# RFID_reader_v2.net
KiCad netlist of a schematic drawn in EAGLE
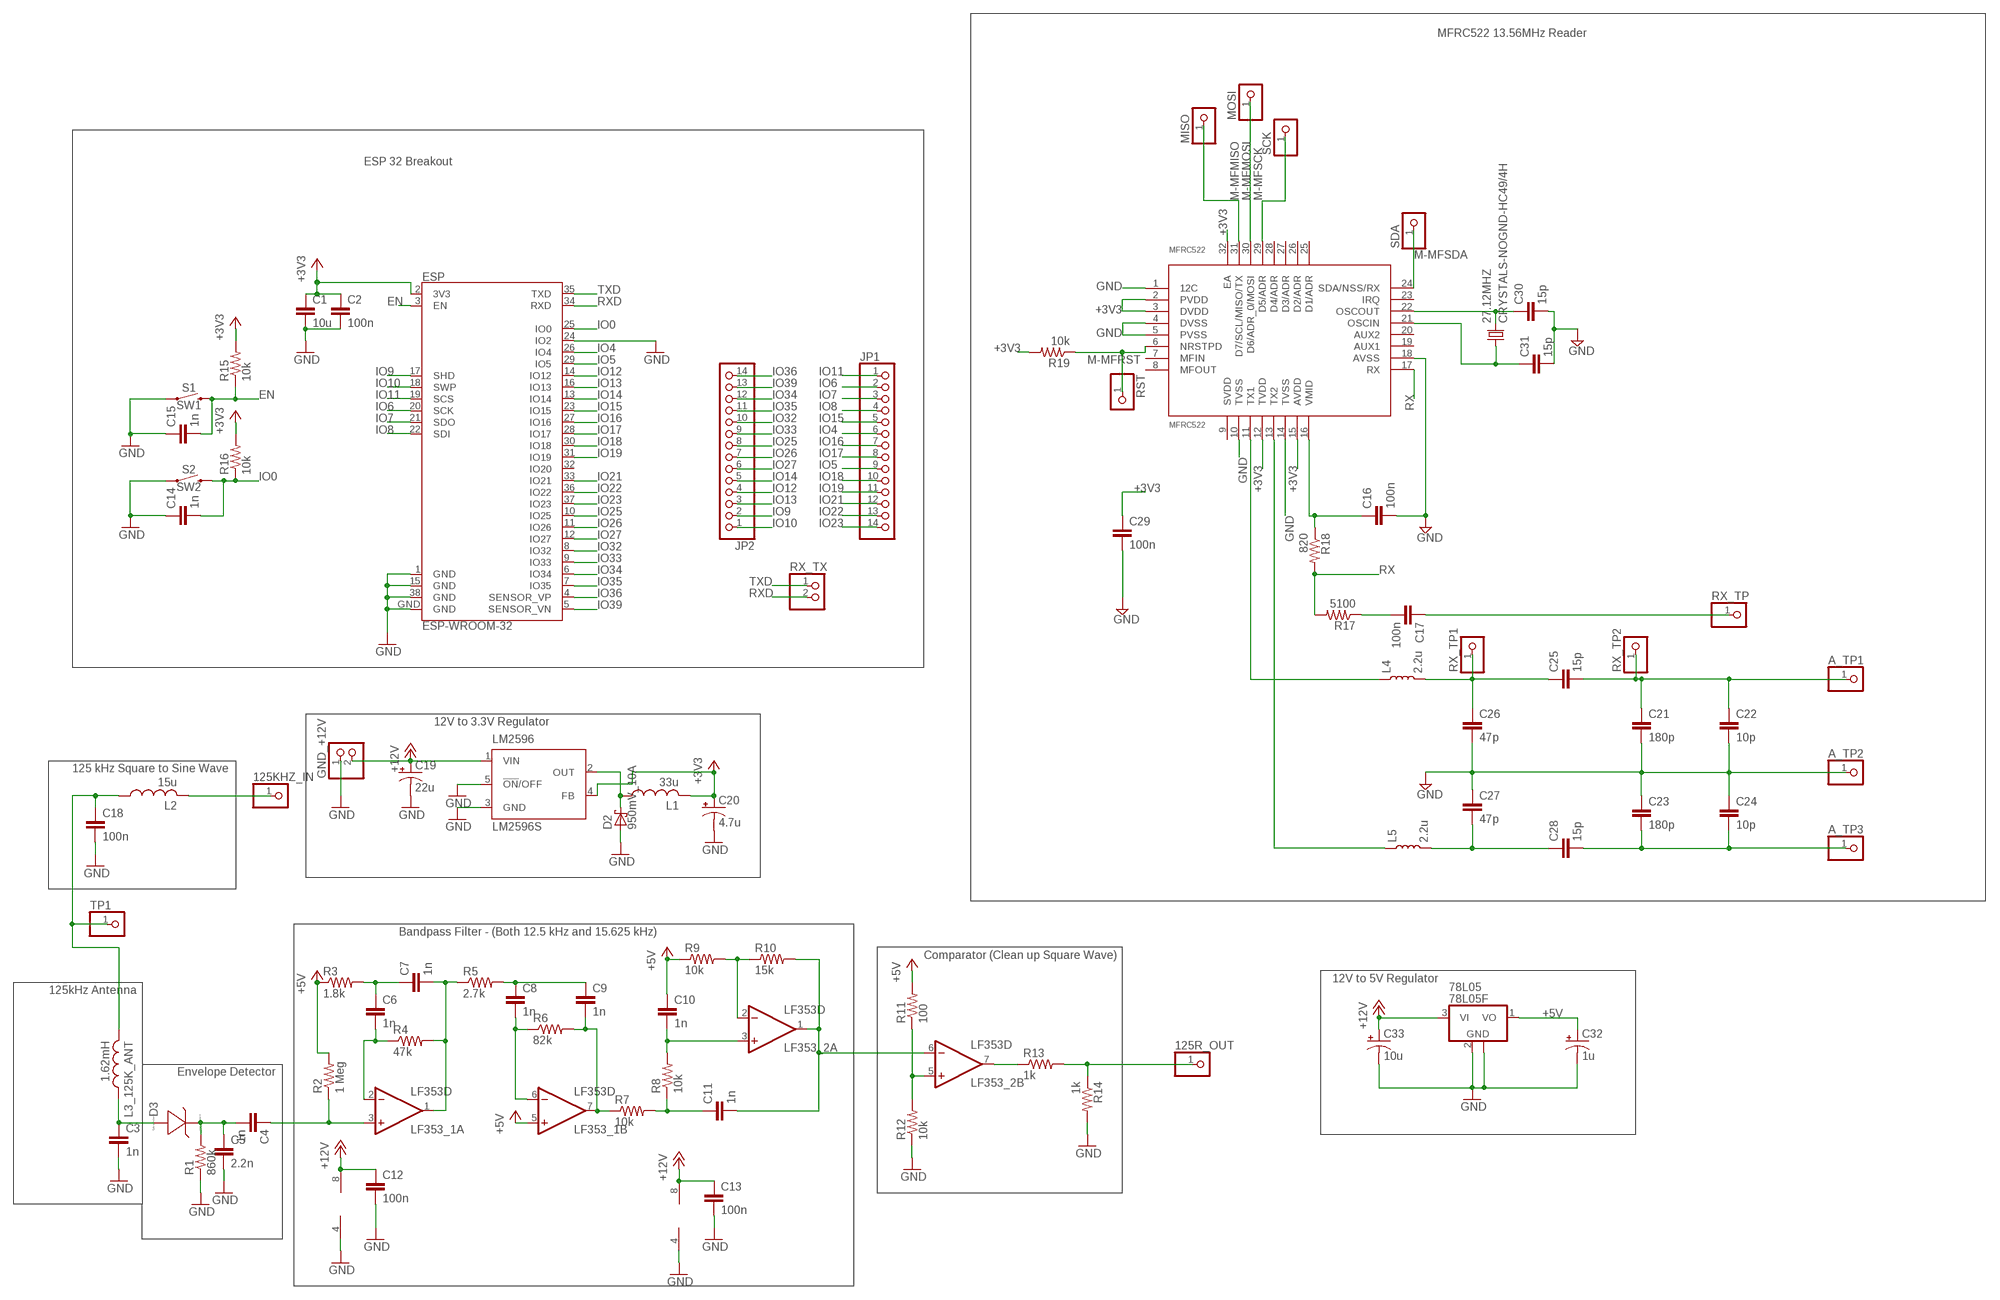
[diagram p0: schematic, sheet 1]

(export (version "E")
  (design (tool "Eeschema 10.0.6"))
  (components
    (comp (ref "27.12MHZ")
      (value "CRYSTALS-NOGND-HC49/4H")
      (footprint "eagle-import:HC49")
      (libsource (lib "eagle-import") (part "CRYSTALS-NOGND-HC49/4H"))
    )
    (comp (ref "78L05")
      (value "78L05F")
      (footprint "eagle-import:SOT89")
      (libsource (lib "eagle-import") (part "78LF05"))
    )
    (comp (ref "125KHZ_IN")
      (value "PINHD-1X1")
      (footprint "eagle-import:1X01")
      (libsource (lib "eagle-import") (part "PINHD-1X1"))
    )
    (comp (ref "125R_OUT")
      (value "PINHD-1X1")
      (footprint "eagle-import:1X01")
      (libsource (lib "eagle-import") (part "PINHD-1X1"))
    )
    (comp (ref "A_TP1")
      (value "PINHD-1X1")
      (footprint "eagle-import:1X01")
      (libsource (lib "eagle-import") (part "PINHD-1X1"))
    )
    (comp (ref "A_TP2")
      (value "PINHD-1X1")
      (footprint "eagle-import:1X01")
      (libsource (lib "eagle-import") (part "PINHD-1X1"))
    )
    (comp (ref "A_TP3")
      (value "PINHD-1X1")
      (footprint "eagle-import:1X01")
      (libsource (lib "eagle-import") (part "PINHD-1X1"))
    )
    (comp (ref "C1")
      (value "10u")
      (footprint "eagle-import:C0805")
      (libsource (lib "eagle-import") (part "C-EUC0805"))
    )
    (comp (ref "C2")
      (value "100n")
      (footprint "eagle-import:C0805")
      (libsource (lib "eagle-import") (part "C-EUC0805"))
    )
    (comp (ref "C3")
      (value "1n")
      (footprint "eagle-import:C0805")
      (libsource (lib "eagle-import") (part "C-EUC0805"))
    )
    (comp (ref "C4")
      (value "1n")
      (footprint "eagle-import:C0805")
      (libsource (lib "eagle-import") (part "C-EUC0805"))
    )
    (comp (ref "C5")
      (value "2.2n")
      (footprint "eagle-import:C0805")
      (libsource (lib "eagle-import") (part "C-EUC0805"))
    )
    (comp (ref "C6")
      (value "1n")
      (footprint "eagle-import:C0805")
      (libsource (lib "eagle-import") (part "C-EUC0805"))
    )
    (comp (ref "C7")
      (value "1n")
      (footprint "eagle-import:C0805")
      (libsource (lib "eagle-import") (part "C-EUC0805"))
    )
    (comp (ref "C8")
      (value "1n")
      (footprint "eagle-import:C0805")
      (libsource (lib "eagle-import") (part "C-EUC0805"))
    )
    (comp (ref "C9")
      (value "1n")
      (footprint "eagle-import:C0805")
      (libsource (lib "eagle-import") (part "C-EUC0805"))
    )
    (comp (ref "C10")
      (value "1n")
      (footprint "eagle-import:C0805")
      (libsource (lib "eagle-import") (part "C-EUC0805"))
    )
    (comp (ref "C11")
      (value "1n")
      (footprint "eagle-import:C0805")
      (libsource (lib "eagle-import") (part "C-EUC0805"))
    )
    (comp (ref "C12")
      (value "100n")
      (footprint "eagle-import:C0805")
      (libsource (lib "eagle-import") (part "C-EUC0805"))
    )
    (comp (ref "C13")
      (value "100n")
      (footprint "eagle-import:C0805")
      (libsource (lib "eagle-import") (part "C-EUC0805"))
    )
    (comp (ref "C14")
      (value "1n")
      (footprint "eagle-import:C0805")
      (libsource (lib "eagle-import") (part "C-EUC0805"))
    )
    (comp (ref "C15")
      (value "1n")
      (footprint "eagle-import:C0805")
      (libsource (lib "eagle-import") (part "C-EUC0805"))
    )
    (comp (ref "C16")
      (value "100n")
      (footprint "eagle-import:C0603")
      (libsource (lib "eagle-import") (part "C-EUC0603"))
    )
    (comp (ref "C17")
      (value "100n")
      (footprint "eagle-import:C0603")
      (libsource (lib "eagle-import") (part "C-EUC0603"))
    )
    (comp (ref "C18")
      (value "100n")
      (footprint "eagle-import:C0805")
      (libsource (lib "eagle-import") (part "C-EUC0805"))
    )
    (comp (ref "C19")
      (value "22u")
      (footprint "eagle-import:SANYO-OSCON_SMD_B6")
      (libsource (lib "eagle-import") (part "CPOL-USSANYO_SMD_B6"))
    )
    (comp (ref "C20")
      (value "4.7u")
      (footprint "eagle-import:SMC_C")
      (libsource (lib "eagle-import") (part "CPOL-USSMCC"))
    )
    (comp (ref "C21")
      (value "180p")
      (footprint "eagle-import:C0603")
      (libsource (lib "eagle-import") (part "C-EUC0603"))
    )
    (comp (ref "C22")
      (value "10p")
      (footprint "eagle-import:C0603")
      (libsource (lib "eagle-import") (part "C-EUC0603"))
    )
    (comp (ref "C23")
      (value "180p")
      (footprint "eagle-import:C0603")
      (libsource (lib "eagle-import") (part "C-EUC0603"))
    )
    (comp (ref "C24")
      (value "10p")
      (footprint "eagle-import:C0603")
      (libsource (lib "eagle-import") (part "C-EUC0603"))
    )
    (comp (ref "C25")
      (value "15p")
      (footprint "eagle-import:C0603")
      (libsource (lib "eagle-import") (part "C-EUC0603"))
    )
    (comp (ref "C26")
      (value "47p")
      (footprint "eagle-import:C0603")
      (libsource (lib "eagle-import") (part "C-EUC0603"))
    )
    (comp (ref "C27")
      (value "47p")
      (footprint "eagle-import:C0603")
      (libsource (lib "eagle-import") (part "C-EUC0603"))
    )
    (comp (ref "C28")
      (value "15p")
      (footprint "eagle-import:C0603")
      (libsource (lib "eagle-import") (part "C-EUC0603"))
    )
    (comp (ref "C29")
      (value "100n")
      (footprint "eagle-import:C0603")
      (libsource (lib "eagle-import") (part "C-EUC0603"))
    )
    (comp (ref "C30")
      (value "15p")
      (footprint "eagle-import:C0603")
      (libsource (lib "eagle-import") (part "C-EUC0603"))
    )
    (comp (ref "C31")
      (value "15p")
      (footprint "eagle-import:C0603")
      (libsource (lib "eagle-import") (part "C-EUC0603"))
    )
    (comp (ref "C32")
      (value "1u")
      (footprint "eagle-import:SMC_A")
      (libsource (lib "eagle-import") (part "CPOL-USSMCA"))
    )
    (comp (ref "C33")
      (value "10u")
      (footprint "eagle-import:SMC_C")
      (libsource (lib "eagle-import") (part "CPOL-USSMCC"))
    )
    (comp (ref "D2")
      (value "950mV_10A")
      (footprint "eagle-import:SMC")
      (libsource (lib "eagle-import") (part "SCHOTTKY-DIODESMC"))
    )
    (comp (ref "D3")
      (value "ZENER")
      (footprint "eagle-import:SOD123")
      (libsource (lib "eagle-import") (part "ZENER"))
    )
    (comp (ref "ESP")
      (value "ESP-WROOM-32")
      (footprint "eagle-import:ESP-WROOM-32")
      (libsource (lib "eagle-import") (part "ESP-WROOM-32"))
    )
    (comp (ref "GND_+12V")
      (value "PINHD-1X2")
      (footprint "eagle-import:1X02")
      (libsource (lib "eagle-import") (part "PINHD-1X2"))
    )
    (comp (ref "JP1")
      (value "PINHD-1X14")
      (footprint "eagle-import:1X14")
      (libsource (lib "eagle-import") (part "PINHD-1X14"))
    )
    (comp (ref "JP2")
      (value "PINHD-1X14")
      (footprint "eagle-import:1X14")
      (libsource (lib "eagle-import") (part "PINHD-1X14"))
    )
    (comp (ref "L1")
      (value "33u")
      (footprint "eagle-import:0207_10")
      (libsource (lib "eagle-import") (part "L-US0207/10"))
    )
    (comp (ref "L2")
      (value "15u")
      (footprint "eagle-import:L2012C")
      (libsource (lib "eagle-import") (part "L-USL2012C"))
    )
    (comp (ref "L3_125K_ANT")
      (value "1.62mH")
      (footprint "eagle-import:0207_10")
      (libsource (lib "eagle-import") (part "L-US0207/10"))
    )
    (comp (ref "L4")
      (value "2.2u")
      (footprint "eagle-import:0603")
      (libsource (lib "eagle-import") (part "INDUCTOR-0603-33NH"))
    )
    (comp (ref "L5")
      (value "2.2u")
      (footprint "eagle-import:0603")
      (libsource (lib "eagle-import") (part "INDUCTOR-0603-33NH"))
    )
    (comp (ref "LF353_1")
      (value "LF353D")
      (footprint "eagle-import:SO08")
      (fields (field (name "SPICEPREFIX") "J"))
      (libsource (lib "eagle-import") (part "LF353D"))
    )
    (comp (ref "LF353_2")
      (value "LF353D")
      (footprint "eagle-import:SO08")
      (libsource (lib "eagle-import") (part "LF353D"))
    )
    (comp (ref "LM2596")
      (value "LM2596S")
      (footprint "eagle-import:TO263-5")
      (fields (field (name "MF") "NATIONAL SEMICONDUCTOR") (field (name "MPN") "LM2596S-ADJ/NOPB"))
      (libsource (lib "eagle-import") (part "LM2596S"))
    )
    (comp (ref "MFRC522")
      (value "MFRC522")
      (footprint "eagle-import:MFR522")
      (libsource (lib "eagle-import") (part "MFRC522"))
    )
    (comp (ref "MISO")
      (value "PINHD-1X1")
      (footprint "eagle-import:1X01")
      (libsource (lib "eagle-import") (part "PINHD-1X1"))
    )
    (comp (ref "MOSI")
      (value "PINHD-1X1")
      (footprint "eagle-import:1X01")
      (libsource (lib "eagle-import") (part "PINHD-1X1"))
    )
    (comp (ref "R1")
      (value "860k")
      (footprint "eagle-import:R0805")
      (libsource (lib "eagle-import") (part "R-US_R0805"))
    )
    (comp (ref "R2")
      (value "1 Meg")
      (footprint "eagle-import:R0805")
      (libsource (lib "eagle-import") (part "R-US_R0805"))
    )
    (comp (ref "R3")
      (value "1.8k")
      (footprint "eagle-import:R0805")
      (libsource (lib "eagle-import") (part "R-US_R0805"))
    )
    (comp (ref "R4")
      (value "47k")
      (footprint "eagle-import:R0805")
      (libsource (lib "eagle-import") (part "R-US_R0805"))
    )
    (comp (ref "R5")
      (value "2.7k")
      (footprint "eagle-import:R0805")
      (libsource (lib "eagle-import") (part "R-US_R0805"))
    )
    (comp (ref "R6")
      (value "82k")
      (footprint "eagle-import:R0805")
      (libsource (lib "eagle-import") (part "R-US_R0805"))
    )
    (comp (ref "R7")
      (value "10k")
      (footprint "eagle-import:R0805")
      (libsource (lib "eagle-import") (part "R-US_R0805"))
    )
    (comp (ref "R8")
      (value "10k")
      (footprint "eagle-import:R0805")
      (libsource (lib "eagle-import") (part "R-US_R0805"))
    )
    (comp (ref "R9")
      (value "10k")
      (footprint "eagle-import:R0805")
      (libsource (lib "eagle-import") (part "R-US_R0805"))
    )
    (comp (ref "R10")
      (value "15k")
      (footprint "eagle-import:R0805")
      (libsource (lib "eagle-import") (part "R-US_R0805"))
    )
    (comp (ref "R11")
      (value "100")
      (footprint "eagle-import:R0805")
      (libsource (lib "eagle-import") (part "R-US_R0805"))
    )
    (comp (ref "R12")
      (value "10k")
      (footprint "eagle-import:R0805")
      (libsource (lib "eagle-import") (part "R-US_R0805"))
    )
    (comp (ref "R13")
      (value "1k")
      (footprint "eagle-import:R0805")
      (libsource (lib "eagle-import") (part "R-US_R0805"))
    )
    (comp (ref "R14")
      (value "1k")
      (footprint "eagle-import:R0805")
      (libsource (lib "eagle-import") (part "R-US_R0805"))
    )
    (comp (ref "R15")
      (value "10k")
      (footprint "eagle-import:R0805")
      (libsource (lib "eagle-import") (part "R-US_R0805"))
    )
    (comp (ref "R16")
      (value "10k")
      (footprint "eagle-import:R0805")
      (libsource (lib "eagle-import") (part "R-US_R0805"))
    )
    (comp (ref "R17")
      (value "5100")
      (footprint "eagle-import:R0603")
      (libsource (lib "eagle-import") (part "R-US_R0603"))
    )
    (comp (ref "R18")
      (value "820")
      (footprint "eagle-import:R0603")
      (libsource (lib "eagle-import") (part "R-US_R0603"))
    )
    (comp (ref "R19")
      (value "10k")
      (footprint "eagle-import:R0603")
      (libsource (lib "eagle-import") (part "R-US_R0603"))
    )
    (comp (ref "RST")
      (value "PINHD-1X1")
      (footprint "eagle-import:1X01")
      (libsource (lib "eagle-import") (part "PINHD-1X1"))
    )
    (comp (ref "RX_TP")
      (value "PINHD-1X1")
      (footprint "eagle-import:1X01")
      (libsource (lib "eagle-import") (part "PINHD-1X1"))
    )
    (comp (ref "RX_TP1")
      (value "PINHD-1X1")
      (footprint "eagle-import:1X01")
      (libsource (lib "eagle-import") (part "PINHD-1X1"))
    )
    (comp (ref "RX_TP2")
      (value "PINHD-1X1")
      (footprint "eagle-import:1X01")
      (libsource (lib "eagle-import") (part "PINHD-1X1"))
    )
    (comp (ref "RX_TX")
      (value "PINHD-1X2")
      (footprint "eagle-import:1X02")
      (libsource (lib "eagle-import") (part "PINHD-1X2"))
    )
    (comp (ref "S1")
      (value "SW1")
      (footprint "eagle-import:TACTILE_SWITCH_SMD_6.0X3.5MM")
      (libsource (lib "eagle-import") (part "MOMENTARY-SWITCH-SPST-SMD-6.0X3.5MM"))
    )
    (comp (ref "S2")
      (value "SW2")
      (footprint "eagle-import:TACTILE_SWITCH_SMD_6.0X3.5MM")
      (libsource (lib "eagle-import") (part "MOMENTARY-SWITCH-SPST-SMD-6.0X3.5MM"))
    )
    (comp (ref "SCK")
      (value "PINHD-1X1")
      (footprint "eagle-import:1X01")
      (libsource (lib "eagle-import") (part "PINHD-1X1"))
    )
    (comp (ref "SDA")
      (value "PINHD-1X1")
      (footprint "eagle-import:1X01")
      (libsource (lib "eagle-import") (part "PINHD-1X1"))
    )
    (comp (ref "TP1")
      (value "PINHD-1X1")
      (footprint "eagle-import:1X01")
      (libsource (lib "eagle-import") (part "PINHD-1X1"))
    )
  )
  (nets
    (net (code "1") (name "+3V3") (class "Default")
      (node (ref "C1") (pin "1") (pinfunction "1_1") (pintype "passive"))
      (node (ref "C2") (pin "1") (pinfunction "1_1") (pintype "passive"))
      (node (ref "C20") (pin "+") (pinfunction "+_+") (pintype "passive"))
      (node (ref "C29") (pin "1") (pinfunction "1_1") (pintype "passive"))
      (node (ref "ESP") (pin "2") (pinfunction "3V3_2") (pintype "bidirectional"))
      (node (ref "L1") (pin "2") (pinfunction "2_2") (pintype "passive"))
      (node (ref "LM2596") (pin "4") (pinfunction "FB_4") (pintype "input"))
      (node (ref "MFRC522") (pin "12") (pinfunction "TVDD_12") (pintype "bidirectional"))
      (node (ref "MFRC522") (pin "15") (pinfunction "AVDD_15") (pintype "bidirectional"))
      (node (ref "MFRC522") (pin "2") (pinfunction "PVDD_2") (pintype "bidirectional"))
      (node (ref "MFRC522") (pin "3") (pinfunction "DVDD_3") (pintype "bidirectional"))
      (node (ref "MFRC522") (pin "32") (pinfunction "EA_32") (pintype "bidirectional"))
      (node (ref "R15") (pin "2") (pinfunction "2_2") (pintype "passive"))
      (node (ref "R16") (pin "2") (pinfunction "2_2") (pintype "passive"))
      (node (ref "R19") (pin "2") (pinfunction "2_2") (pintype "passive"))
    )
    (net (code "2") (name "+5V") (class "Default")
      (node (ref "78L05") (pin "1") (pinfunction "VO_1") (pintype "passive"))
      (node (ref "C10") (pin "1") (pinfunction "1_1") (pintype "passive"))
      (node (ref "C32") (pin "+") (pinfunction "+_+") (pintype "passive"))
      (node (ref "LF353_1") (pin "5") (pinfunction "+IN_5") (pintype "input"))
      (node (ref "R11") (pin "2") (pinfunction "2_2") (pintype "passive"))
      (node (ref "R2") (pin "2") (pinfunction "2_2") (pintype "passive"))
      (node (ref "R3") (pin "1") (pinfunction "1_1") (pintype "passive"))
      (node (ref "R9") (pin "1") (pinfunction "1_1") (pintype "passive"))
    )
    (net (code "3") (name "+12V") (class "Default")
      (node (ref "78L05") (pin "3") (pinfunction "VI_3") (pintype "input"))
      (node (ref "C12") (pin "1") (pinfunction "1_1") (pintype "passive"))
      (node (ref "C13") (pin "1") (pinfunction "1_1") (pintype "passive"))
      (node (ref "C19") (pin "+") (pinfunction "+_+") (pintype "passive"))
      (node (ref "C33") (pin "+") (pinfunction "+_+") (pintype "passive"))
      (node (ref "GND_+12V") (pin "2") (pinfunction "2_2") (pintype "passive"))
      (node (ref "LF353_1") (pin "8") (pinfunction "V+_8") (pintype "power_in"))
      (node (ref "LF353_2") (pin "8") (pinfunction "V+_8") (pintype "power_in"))
      (node (ref "LM2596") (pin "1") (pinfunction "VIN_1") (pintype "input"))
    )
    (net (code "4") (name "/EN") (class "Default")
      (node (ref "C15") (pin "2") (pinfunction "2_2") (pintype "passive"))
      (node (ref "ESP") (pin "3") (pinfunction "EN_3") (pintype "bidirectional"))
      (node (ref "R15") (pin "1") (pinfunction "1_1") (pintype "passive"))
      (node (ref "S1") (pin "2") (pinfunction "2_2") (pintype "passive"))
    )
    (net (code "5") (name "/IO0") (class "Default")
      (node (ref "C14") (pin "2") (pinfunction "2_2") (pintype "passive"))
      (node (ref "ESP") (pin "25") (pinfunction "IO0_25") (pintype "bidirectional"))
      (node (ref "R16") (pin "1") (pinfunction "1_1") (pintype "passive"))
      (node (ref "S2") (pin "2") (pinfunction "2_2") (pintype "passive"))
    )
    (net (code "6") (name "/IO4") (class "Default")
      (node (ref "ESP") (pin "26") (pinfunction "IO4_26") (pintype "bidirectional"))
      (node (ref "JP1") (pin "6") (pinfunction "6_6") (pintype "passive"))
    )
    (net (code "7") (name "/IO5") (class "Default")
      (node (ref "ESP") (pin "29") (pinfunction "IO5_29") (pintype "bidirectional"))
      (node (ref "JP1") (pin "9") (pinfunction "9_9") (pintype "passive"))
    )
    (net (code "8") (name "/IO6") (class "Default")
      (node (ref "ESP") (pin "20") (pinfunction "SCK_20") (pintype "bidirectional"))
      (node (ref "JP1") (pin "2") (pinfunction "2_2") (pintype "passive"))
    )
    (net (code "9") (name "/IO7") (class "Default")
      (node (ref "ESP") (pin "21") (pinfunction "SDO_21") (pintype "bidirectional"))
      (node (ref "JP1") (pin "3") (pinfunction "3_3") (pintype "passive"))
    )
    (net (code "10") (name "/IO8") (class "Default")
      (node (ref "ESP") (pin "22") (pinfunction "SDI_22") (pintype "bidirectional"))
      (node (ref "JP1") (pin "4") (pinfunction "4_4") (pintype "passive"))
    )
    (net (code "11") (name "/IO9") (class "Default")
      (node (ref "ESP") (pin "17") (pinfunction "SHD_17") (pintype "bidirectional"))
      (node (ref "JP2") (pin "2") (pinfunction "2_2") (pintype "passive"))
    )
    (net (code "12") (name "/IO10") (class "Default")
      (node (ref "ESP") (pin "18") (pinfunction "SWP_18") (pintype "bidirectional"))
      (node (ref "JP2") (pin "1") (pinfunction "1_1") (pintype "passive"))
    )
    (net (code "13") (name "/IO11") (class "Default")
      (node (ref "ESP") (pin "19") (pinfunction "SCS_19") (pintype "bidirectional"))
      (node (ref "JP1") (pin "1") (pinfunction "1_1") (pintype "passive"))
    )
    (net (code "14") (name "/IO12") (class "Default")
      (node (ref "ESP") (pin "14") (pinfunction "IO12_14") (pintype "bidirectional"))
      (node (ref "JP2") (pin "4") (pinfunction "4_4") (pintype "passive"))
    )
    (net (code "15") (name "/IO13") (class "Default")
      (node (ref "ESP") (pin "16") (pinfunction "IO13_16") (pintype "bidirectional"))
      (node (ref "JP2") (pin "3") (pinfunction "3_3") (pintype "passive"))
    )
    (net (code "16") (name "/IO14") (class "Default")
      (node (ref "ESP") (pin "13") (pinfunction "IO14_13") (pintype "bidirectional"))
      (node (ref "JP2") (pin "5") (pinfunction "5_5") (pintype "passive"))
    )
    (net (code "17") (name "/IO15") (class "Default")
      (node (ref "ESP") (pin "23") (pinfunction "IO15_23") (pintype "bidirectional"))
      (node (ref "JP1") (pin "5") (pinfunction "5_5") (pintype "passive"))
    )
    (net (code "18") (name "/IO16") (class "Default")
      (node (ref "ESP") (pin "27") (pinfunction "IO16_27") (pintype "bidirectional"))
      (node (ref "JP1") (pin "7") (pinfunction "7_7") (pintype "passive"))
    )
    (net (code "19") (name "/IO17") (class "Default")
      (node (ref "ESP") (pin "28") (pinfunction "IO17_28") (pintype "bidirectional"))
      (node (ref "JP1") (pin "8") (pinfunction "8_8") (pintype "passive"))
    )
    (net (code "20") (name "/IO18") (class "Default")
      (node (ref "ESP") (pin "30") (pinfunction "IO18_30") (pintype "bidirectional"))
      (node (ref "JP1") (pin "10") (pinfunction "10_10") (pintype "passive"))
    )
    (net (code "21") (name "/IO19") (class "Default")
      (node (ref "ESP") (pin "31") (pinfunction "IO19_31") (pintype "bidirectional"))
      (node (ref "JP1") (pin "11") (pinfunction "11_11") (pintype "passive"))
    )
    (net (code "22") (name "/IO21") (class "Default")
      (node (ref "ESP") (pin "33") (pinfunction "IO21_33") (pintype "bidirectional"))
      (node (ref "JP1") (pin "12") (pinfunction "12_12") (pintype "passive"))
    )
    (net (code "23") (name "/IO22") (class "Default")
      (node (ref "ESP") (pin "36") (pinfunction "IO22_36") (pintype "bidirectional"))
      (node (ref "JP1") (pin "13") (pinfunction "13_13") (pintype "passive"))
    )
    (net (code "24") (name "/IO23") (class "Default")
      (node (ref "ESP") (pin "37") (pinfunction "IO23_37") (pintype "bidirectional"))
      (node (ref "JP1") (pin "14") (pinfunction "14_14") (pintype "passive"))
    )
    (net (code "25") (name "/IO25") (class "Default")
      (node (ref "ESP") (pin "10") (pinfunction "IO25_10") (pintype "bidirectional"))
      (node (ref "JP2") (pin "8") (pinfunction "8_8") (pintype "passive"))
    )
    (net (code "26") (name "/IO26") (class "Default")
      (node (ref "ESP") (pin "11") (pinfunction "IO26_11") (pintype "bidirectional"))
      (node (ref "JP2") (pin "7") (pinfunction "7_7") (pintype "passive"))
    )
    (net (code "27") (name "/IO27") (class "Default")
      (node (ref "ESP") (pin "12") (pinfunction "IO27_12") (pintype "bidirectional"))
      (node (ref "JP2") (pin "6") (pinfunction "6_6") (pintype "passive"))
    )
    (net (code "28") (name "/IO32") (class "Default")
      (node (ref "ESP") (pin "8") (pinfunction "IO32_8") (pintype "bidirectional"))
      (node (ref "JP2") (pin "10") (pinfunction "10_10") (pintype "passive"))
    )
    (net (code "29") (name "/IO33") (class "Default")
      (node (ref "ESP") (pin "9") (pinfunction "IO33_9") (pintype "bidirectional"))
      (node (ref "JP2") (pin "9") (pinfunction "9_9") (pintype "passive"))
    )
    (net (code "30") (name "/IO34") (class "Default")
      (node (ref "ESP") (pin "6") (pinfunction "IO34_6") (pintype "bidirectional"))
      (node (ref "JP2") (pin "12") (pinfunction "12_12") (pintype "passive"))
    )
    (net (code "31") (name "/IO35") (class "Default")
      (node (ref "ESP") (pin "7") (pinfunction "IO35_7") (pintype "bidirectional"))
      (node (ref "JP2") (pin "11") (pinfunction "11_11") (pintype "passive"))
    )
    (net (code "32") (name "/IO36") (class "Default")
      (node (ref "ESP") (pin "4") (pinfunction "SENSOR_VP_4") (pintype "bidirectional"))
      (node (ref "JP2") (pin "14") (pinfunction "14_14") (pintype "passive"))
    )
    (net (code "33") (name "/IO39") (class "Default")
      (node (ref "ESP") (pin "5") (pinfunction "SENSOR_VN_5") (pintype "bidirectional"))
      (node (ref "JP2") (pin "13") (pinfunction "13_13") (pintype "passive"))
    )
    (net (code "34") (name "/M-MFMISO") (class "Default")
      (node (ref "MFRC522") (pin "31") (pinfunction "D7/SCL/MISO/TX_31") (pintype "bidirectional"))
      (node (ref "MISO") (pin "1") (pinfunction "1_1") (pintype "passive"))
    )
    (net (code "35") (name "/M-MFMOSI") (class "Default")
      (node (ref "MFRC522") (pin "30") (pinfunction "D6/ADR_0/MOSI_30") (pintype "bidirectional"))
      (node (ref "MOSI") (pin "1") (pinfunction "1_1") (pintype "passive"))
    )
    (net (code "36") (name "/M-MFRST") (class "Default")
      (node (ref "MFRC522") (pin "6") (pinfunction "NRSTPD_6") (pintype "bidirectional"))
      (node (ref "R19") (pin "1") (pinfunction "1_1") (pintype "passive"))
      (node (ref "RST") (pin "1") (pinfunction "1_1") (pintype "passive"))
    )
    (net (code "37") (name "/M-MFSCK") (class "Default")
      (node (ref "MFRC522") (pin "29") (pinfunction "D5/ADR_29") (pintype "bidirectional"))
      (node (ref "SCK") (pin "1") (pinfunction "1_1") (pintype "passive"))
    )
    (net (code "38") (name "/M-MFSDA") (class "Default")
      (node (ref "MFRC522") (pin "24") (pinfunction "SDA/NSS/RX_24") (pintype "bidirectional"))
      (node (ref "SDA") (pin "1") (pinfunction "1_1") (pintype "passive"))
    )
    (net (code "39") (name "/RX") (class "Default")
      (node (ref "MFRC522") (pin "17") (pinfunction "RX_17") (pintype "bidirectional"))
      (node (ref "R17") (pin "2") (pinfunction "2_2") (pintype "passive"))
      (node (ref "R18") (pin "2") (pinfunction "2_2") (pintype "passive"))
    )
    (net (code "40") (name "/RXD") (class "Default")
      (node (ref "ESP") (pin "34") (pinfunction "RXD_34") (pintype "bidirectional"))
      (node (ref "RX_TX") (pin "2") (pinfunction "2_2") (pintype "passive"))
    )
    (net (code "41") (name "/TXD") (class "Default")
      (node (ref "ESP") (pin "35") (pinfunction "TXD_35") (pintype "bidirectional"))
      (node (ref "RX_TX") (pin "1") (pinfunction "1_1") (pintype "passive"))
    )
    (net (code "42") (name "GND") (class "Default")
      (node (ref "78L05") (pin "2") (pinfunction "GND_2") (pintype "passive"))
      (node (ref "78L05") (pin "2@1") (pinfunction "GND_2@1") (pintype "passive"))
      (node (ref "A_TP2") (pin "1") (pinfunction "1_1") (pintype "passive"))
      (node (ref "C1") (pin "2") (pinfunction "2_2") (pintype "passive"))
      (node (ref "C12") (pin "2") (pinfunction "2_2") (pintype "passive"))
      (node (ref "C13") (pin "2") (pinfunction "2_2") (pintype "passive"))
      (node (ref "C14") (pin "1") (pinfunction "1_1") (pintype "passive"))
      (node (ref "C15") (pin "1") (pinfunction "1_1") (pintype "passive"))
      (node (ref "C16") (pin "2") (pinfunction "2_2") (pintype "passive"))
      (node (ref "C18") (pin "2") (pinfunction "2_2") (pintype "passive"))
      (node (ref "C19") (pin "-") (pinfunction "-_-") (pintype "passive"))
      (node (ref "C2") (pin "2") (pinfunction "2_2") (pintype "passive"))
      (node (ref "C20") (pin "-") (pinfunction "-_-") (pintype "passive"))
      (node (ref "C21") (pin "2") (pinfunction "2_2") (pintype "passive"))
      (node (ref "C22") (pin "2") (pinfunction "2_2") (pintype "passive"))
      (node (ref "C23") (pin "1") (pinfunction "1_1") (pintype "passive"))
      (node (ref "C24") (pin "1") (pinfunction "1_1") (pintype "passive"))
      (node (ref "C26") (pin "2") (pinfunction "2_2") (pintype "passive"))
      (node (ref "C27") (pin "1") (pinfunction "1_1") (pintype "passive"))
      (node (ref "C29") (pin "2") (pinfunction "2_2") (pintype "passive"))
      (node (ref "C3") (pin "2") (pinfunction "2_2") (pintype "passive"))
      (node (ref "C30") (pin "2") (pinfunction "2_2") (pintype "passive"))
      (node (ref "C31") (pin "2") (pinfunction "2_2") (pintype "passive"))
      (node (ref "C32") (pin "-") (pinfunction "-_-") (pintype "passive"))
      (node (ref "C33") (pin "-") (pinfunction "-_-") (pintype "passive"))
      (node (ref "C5") (pin "2") (pinfunction "2_2") (pintype "passive"))
      (node (ref "D2") (pin "A") (pinfunction "A_A") (pintype "passive"))
      (node (ref "ESP") (pin "1") (pinfunction "GND_1") (pintype "bidirectional"))
      (node (ref "ESP") (pin "15") (pinfunction "GND_15") (pintype "bidirectional"))
      (node (ref "ESP") (pin "24") (pinfunction "IO2_24") (pintype "bidirectional"))
      (node (ref "ESP") (pin "38") (pinfunction "GND_38") (pintype "bidirectional"))
      (node (ref "ESP") (pin "GND") (pinfunction "GND_GND") (pintype "bidirectional"))
      (node (ref "GND_+12V") (pin "1") (pinfunction "1_1") (pintype "passive"))
      (node (ref "LF353_1") (pin "4") (pinfunction "V-_4") (pintype "power_in"))
      (node (ref "LF353_2") (pin "4") (pinfunction "V-_4") (pintype "power_in"))
      (node (ref "LM2596") (pin "3") (pinfunction "GND_3") (pintype "power_in"))
      (node (ref "LM2596") (pin "5") (pinfunction "~{ON}/OFF_5") (pintype "input"))
      (node (ref "MFRC522") (pin "1") (pinfunction "12C_1") (pintype "bidirectional"))
      (node (ref "MFRC522") (pin "10") (pinfunction "TVSS_10") (pintype "bidirectional"))
      (node (ref "MFRC522") (pin "14") (pinfunction "TVSS_14") (pintype "bidirectional"))
      (node (ref "MFRC522") (pin "18") (pinfunction "AVSS_18") (pintype "bidirectional"))
      (node (ref "MFRC522") (pin "4") (pinfunction "DVSS_4") (pintype "bidirectional"))
      (node (ref "MFRC522") (pin "5") (pinfunction "PVSS_5") (pintype "bidirectional"))
      (node (ref "R1") (pin "1") (pinfunction "1_1") (pintype "passive"))
      (node (ref "R12") (pin "1") (pinfunction "1_1") (pintype "passive"))
      (node (ref "R14") (pin "2") (pinfunction "2_2") (pintype "passive"))
      (node (ref "S1") (pin "1") (pinfunction "1_1") (pintype "passive"))
      (node (ref "S2") (pin "1") (pinfunction "1_1") (pintype "passive"))
    )
    (net (code "43") (name "Net-(125KHZ_IN-Pad1)") (class "Default")
      (node (ref "125KHZ_IN") (pin "1") (pinfunction "1_1") (pintype "passive"))
      (node (ref "L2") (pin "2") (pinfunction "2_2") (pintype "passive"))
    )
    (net (code "44") (name "Net-(125R_OUT-Pad1)") (class "Default")
      (node (ref "125R_OUT") (pin "1") (pinfunction "1_1") (pintype "passive"))
      (node (ref "R13") (pin "2") (pinfunction "2_2") (pintype "passive"))
      (node (ref "R14") (pin "1") (pinfunction "1_1") (pintype "passive"))
    )
    (net (code "45") (name "Net-(A_TP1-Pad1)") (class "Default")
      (node (ref "A_TP1") (pin "1") (pinfunction "1_1") (pintype "passive"))
      (node (ref "C21") (pin "1") (pinfunction "1_1") (pintype "passive"))
      (node (ref "C22") (pin "1") (pinfunction "1_1") (pintype "passive"))
      (node (ref "C25") (pin "2") (pinfunction "2_2") (pintype "passive"))
      (node (ref "RX_TP2") (pin "1") (pinfunction "1_1") (pintype "passive"))
    )
    (net (code "46") (name "Net-(A_TP3-Pad1)") (class "Default")
      (node (ref "A_TP3") (pin "1") (pinfunction "1_1") (pintype "passive"))
      (node (ref "C23") (pin "2") (pinfunction "2_2") (pintype "passive"))
      (node (ref "C24") (pin "2") (pinfunction "2_2") (pintype "passive"))
      (node (ref "C28") (pin "2") (pinfunction "2_2") (pintype "passive"))
    )
    (net (code "47") (name "Net-(C6-Pad1)") (class "Default")
      (node (ref "C6") (pin "1") (pinfunction "1_1") (pintype "passive"))
      (node (ref "C7") (pin "1") (pinfunction "1_1") (pintype "passive"))
      (node (ref "R3") (pin "2") (pinfunction "2_2") (pintype "passive"))
    )
    (net (code "48") (name "Net-(C8-Pad1)") (class "Default")
      (node (ref "C8") (pin "1") (pinfunction "1_1") (pintype "passive"))
      (node (ref "C9") (pin "1") (pinfunction "1_1") (pintype "passive"))
      (node (ref "R5") (pin "2") (pinfunction "2_2") (pintype "passive"))
    )
    (net (code "49") (name "Net-(C11-Pad1)") (class "Default")
      (node (ref "C11") (pin "1") (pinfunction "1_1") (pintype "passive"))
      (node (ref "R7") (pin "2") (pinfunction "2_2") (pintype "passive"))
      (node (ref "R8") (pin "1") (pinfunction "1_1") (pintype "passive"))
    )
    (net (code "50") (name "Net-(C17-Pad1)") (class "Default")
      (node (ref "C17") (pin "1") (pinfunction "1_1") (pintype "passive"))
      (node (ref "RX_TP") (pin "1") (pinfunction "1_1") (pintype "passive"))
    )
    (net (code "51") (name "Net-(C17-Pad2)") (class "Default")
      (node (ref "C17") (pin "2") (pinfunction "2_2") (pintype "passive"))
      (node (ref "R17") (pin "1") (pinfunction "1_1") (pintype "passive"))
    )
    (net (code "52") (name "Net-(C18-Pad1)") (class "Default")
      (node (ref "C18") (pin "1") (pinfunction "1_1") (pintype "passive"))
      (node (ref "L2") (pin "1") (pinfunction "1_1") (pintype "passive"))
      (node (ref "L3_125K_ANT") (pin "2") (pinfunction "2_2") (pintype "passive"))
      (node (ref "TP1") (pin "1") (pinfunction "1_1") (pintype "passive"))
    )
    (net (code "53") (name "Net-(C25-Pad1)") (class "Default")
      (node (ref "C25") (pin "1") (pinfunction "1_1") (pintype "passive"))
      (node (ref "C26") (pin "1") (pinfunction "1_1") (pintype "passive"))
      (node (ref "L4") (pin "2") (pinfunction "2_2") (pintype "passive"))
      (node (ref "RX_TP1") (pin "1") (pinfunction "1_1") (pintype "passive"))
    )
    (net (code "54") (name "Net-(C27-Pad2)") (class "Default")
      (node (ref "C27") (pin "2") (pinfunction "2_2") (pintype "passive"))
      (node (ref "C28") (pin "1") (pinfunction "1_1") (pintype "passive"))
      (node (ref "L5") (pin "2") (pinfunction "2_2") (pintype "passive"))
    )
    (net (code "55") (name "Net-(D3-+)") (class "Default")
      (node (ref "C3") (pin "1") (pinfunction "1_1") (pintype "passive"))
      (node (ref "D3") (pin "A") (pinfunction "+_A") (pintype "passive"))
      (node (ref "L3_125K_ANT") (pin "1") (pinfunction "1_1") (pintype "passive"))
    )
    (net (code "56") (name "Net-(D3--)") (class "Default")
      (node (ref "C4") (pin "2") (pinfunction "2_2") (pintype "passive"))
      (node (ref "C5") (pin "1") (pinfunction "1_1") (pintype "passive"))
      (node (ref "D3") (pin "C") (pinfunction "-_C") (pintype "passive"))
      (node (ref "R1") (pin "2") (pinfunction "2_2") (pintype "passive"))
    )
    (net (code "57") (name "Net-(LF353_1A-+IN)") (class "Default")
      (node (ref "C4") (pin "1") (pinfunction "1_1") (pintype "passive"))
      (node (ref "LF353_1") (pin "3") (pinfunction "+IN_3") (pintype "input"))
      (node (ref "R2") (pin "1") (pinfunction "1_1") (pintype "passive"))
    )
    (net (code "58") (name "Net-(LF353_1A--IN)") (class "Default")
      (node (ref "C6") (pin "2") (pinfunction "2_2") (pintype "passive"))
      (node (ref "LF353_1") (pin "2") (pinfunction "-IN_2") (pintype "input"))
      (node (ref "R4") (pin "1") (pinfunction "1_1") (pintype "passive"))
    )
    (net (code "59") (name "Net-(LF353_1A-OUT)") (class "Default")
      (node (ref "C7") (pin "2") (pinfunction "2_2") (pintype "passive"))
      (node (ref "LF353_1") (pin "1") (pinfunction "OUT_1") (pintype "output"))
      (node (ref "R4") (pin "2") (pinfunction "2_2") (pintype "passive"))
      (node (ref "R5") (pin "1") (pinfunction "1_1") (pintype "passive"))
    )
    (net (code "60") (name "Net-(LF353_1B--IN)") (class "Default")
      (node (ref "C8") (pin "2") (pinfunction "2_2") (pintype "passive"))
      (node (ref "LF353_1") (pin "6") (pinfunction "-IN_6") (pintype "input"))
      (node (ref "R6") (pin "1") (pinfunction "1_1") (pintype "passive"))
    )
    (net (code "61") (name "Net-(LF353_1B-OUT)") (class "Default")
      (node (ref "C9") (pin "2") (pinfunction "2_2") (pintype "passive"))
      (node (ref "LF353_1") (pin "7") (pinfunction "OUT_7") (pintype "output"))
      (node (ref "R6") (pin "2") (pinfunction "2_2") (pintype "passive"))
      (node (ref "R7") (pin "1") (pinfunction "1_1") (pintype "passive"))
    )
    (net (code "62") (name "Net-(LF353_2A-+IN)") (class "Default")
      (node (ref "C10") (pin "2") (pinfunction "2_2") (pintype "passive"))
      (node (ref "LF353_2") (pin "3") (pinfunction "+IN_3") (pintype "input"))
      (node (ref "R8") (pin "2") (pinfunction "2_2") (pintype "passive"))
    )
    (net (code "63") (name "Net-(LF353_2A--IN)") (class "Default")
      (node (ref "LF353_2") (pin "2") (pinfunction "-IN_2") (pintype "input"))
      (node (ref "R10") (pin "1") (pinfunction "1_1") (pintype "passive"))
      (node (ref "R9") (pin "2") (pinfunction "2_2") (pintype "passive"))
    )
    (net (code "64") (name "Net-(LF353_2A-OUT)") (class "Default")
      (node (ref "C11") (pin "2") (pinfunction "2_2") (pintype "passive"))
      (node (ref "LF353_2") (pin "1") (pinfunction "OUT_1") (pintype "output"))
      (node (ref "LF353_2") (pin "6") (pinfunction "-IN_6") (pintype "input"))
      (node (ref "R10") (pin "2") (pinfunction "2_2") (pintype "passive"))
    )
    (net (code "65") (name "Net-(LF353_2B-+IN)") (class "Default")
      (node (ref "LF353_2") (pin "5") (pinfunction "+IN_5") (pintype "input"))
      (node (ref "R11") (pin "1") (pinfunction "1_1") (pintype "passive"))
      (node (ref "R12") (pin "2") (pinfunction "2_2") (pintype "passive"))
    )
    (net (code "66") (name "Net-(LF353_2B-OUT)") (class "Default")
      (node (ref "LF353_2") (pin "7") (pinfunction "OUT_7") (pintype "output"))
      (node (ref "R13") (pin "1") (pinfunction "1_1") (pintype "passive"))
    )
    (net (code "67") (name "Net-(LM2596-OUT)") (class "Default")
      (node (ref "D2") (pin "C") (pinfunction "C_C") (pintype "passive"))
      (node (ref "L1") (pin "1") (pinfunction "1_1") (pintype "passive"))
      (node (ref "LM2596") (pin "2") (pinfunction "OUT_2") (pintype "output"))
    )
    (net (code "68") (name "Net-(MFRC522-OSCIN)") (class "Default")
      (node (ref "27.12MHZ") (pin "1") (pinfunction "1_1") (pintype "passive"))
      (node (ref "C31") (pin "1") (pinfunction "1_1") (pintype "passive"))
      (node (ref "MFRC522") (pin "21") (pinfunction "OSCIN_21") (pintype "bidirectional"))
    )
    (net (code "69") (name "Net-(MFRC522-OSCOUT)") (class "Default")
      (node (ref "27.12MHZ") (pin "2") (pinfunction "2_2") (pintype "passive"))
      (node (ref "C30") (pin "1") (pinfunction "1_1") (pintype "passive"))
      (node (ref "MFRC522") (pin "22") (pinfunction "OSCOUT_22") (pintype "bidirectional"))
    )
    (net (code "70") (name "Net-(MFRC522-TX1)") (class "Default")
      (node (ref "L4") (pin "1") (pinfunction "1_1") (pintype "passive"))
      (node (ref "MFRC522") (pin "11") (pinfunction "TX1_11") (pintype "bidirectional"))
    )
    (net (code "71") (name "Net-(MFRC522-TX2)") (class "Default")
      (node (ref "L5") (pin "1") (pinfunction "1_1") (pintype "passive"))
      (node (ref "MFRC522") (pin "13") (pinfunction "TX2_13") (pintype "bidirectional"))
    )
    (net (code "72") (name "Net-(MFRC522-VMID)") (class "Default")
      (node (ref "C16") (pin "1") (pinfunction "1_1") (pintype "passive"))
      (node (ref "MFRC522") (pin "16") (pinfunction "VMID_16") (pintype "bidirectional"))
      (node (ref "R18") (pin "1") (pinfunction "1_1") (pintype "passive"))
    )
    (net (code "73") (name "unconnected-(ESP-IO20-Pad32)") (class "Default")
      (node (ref "ESP") (pin "32") (pinfunction "IO20_32") (pintype "bidirectional"))
    )
    (net (code "74") (name "unconnected-(MFRC522-AUX1-Pad19)") (class "Default")
      (node (ref "MFRC522") (pin "19") (pinfunction "AUX1_19") (pintype "bidirectional"))
    )
    (net (code "75") (name "unconnected-(MFRC522-AUX2-Pad20)") (class "Default")
      (node (ref "MFRC522") (pin "20") (pinfunction "AUX2_20") (pintype "bidirectional"))
    )
    (net (code "76") (name "unconnected-(MFRC522-D1{slash}ADR-Pad25)") (class "Default")
      (node (ref "MFRC522") (pin "25") (pinfunction "D1/ADR_25") (pintype "bidirectional"))
    )
    (net (code "77") (name "unconnected-(MFRC522-D2{slash}ADR-Pad26)") (class "Default")
      (node (ref "MFRC522") (pin "26") (pinfunction "D2/ADR_26") (pintype "bidirectional"))
    )
    (net (code "78") (name "unconnected-(MFRC522-D3{slash}ADR-Pad27)") (class "Default")
      (node (ref "MFRC522") (pin "27") (pinfunction "D3/ADR_27") (pintype "bidirectional"))
    )
    (net (code "79") (name "unconnected-(MFRC522-D4{slash}ADR-Pad28)") (class "Default")
      (node (ref "MFRC522") (pin "28") (pinfunction "D4/ADR_28") (pintype "bidirectional"))
    )
    (net (code "80") (name "unconnected-(MFRC522-IRQ-Pad23)") (class "Default")
      (node (ref "MFRC522") (pin "23") (pinfunction "IRQ_23") (pintype "bidirectional"))
    )
    (net (code "81") (name "unconnected-(MFRC522-MFIN-Pad7)") (class "Default")
      (node (ref "MFRC522") (pin "7") (pinfunction "MFIN_7") (pintype "bidirectional"))
    )
    (net (code "82") (name "unconnected-(MFRC522-MFOUT-Pad8)") (class "Default")
      (node (ref "MFRC522") (pin "8") (pinfunction "MFOUT_8") (pintype "bidirectional"))
    )
    (net (code "83") (name "unconnected-(MFRC522-SVDD-Pad9)") (class "Default")
      (node (ref "MFRC522") (pin "9") (pinfunction "SVDD_9") (pintype "bidirectional"))
    )
  )
)
